# stepped-tone-generator.net
KiCad netlist of a schematic drawn in EAGLE
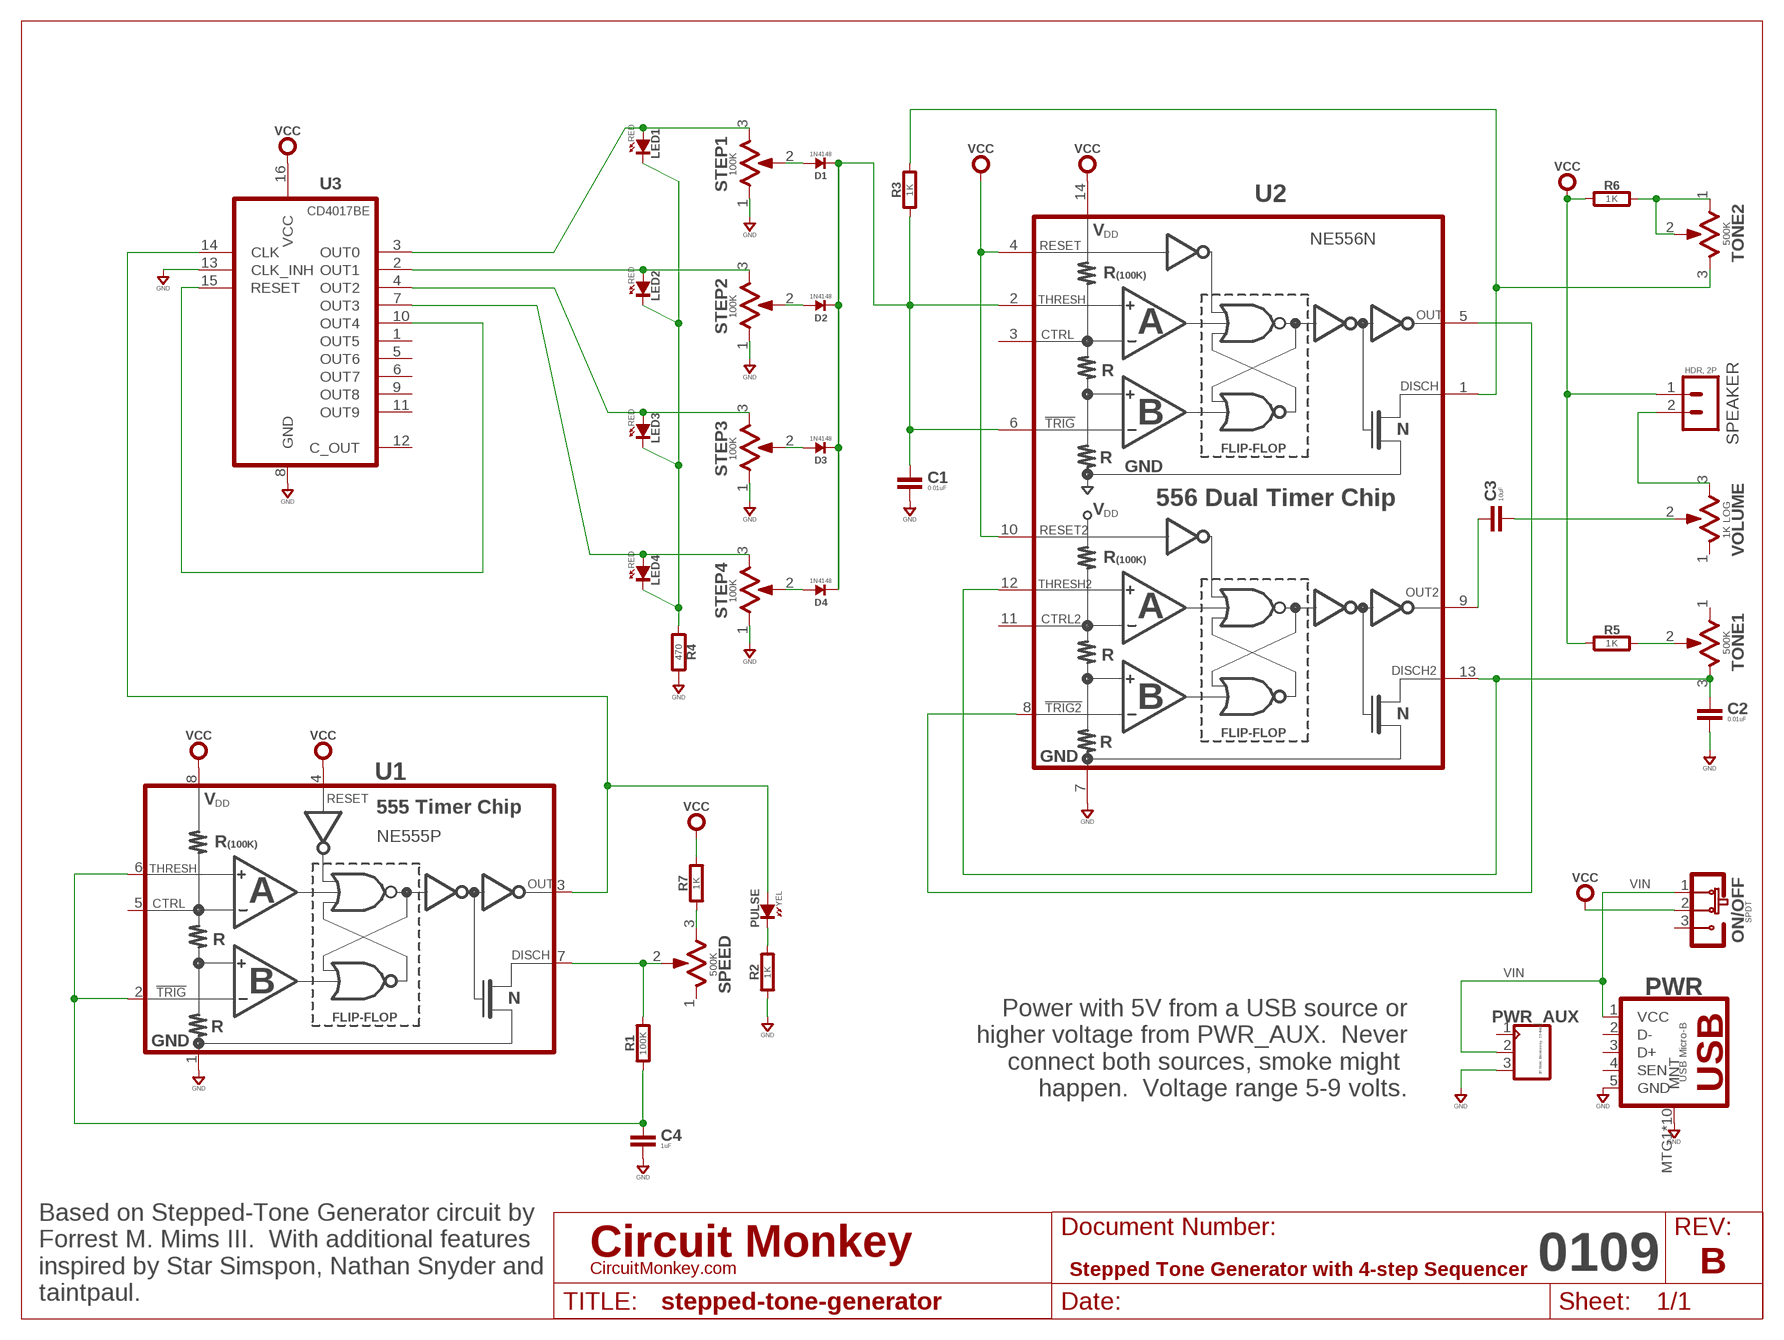
[diagram p0: schematic, sheet 1]

(export (version "E")
  (design (tool "Eeschema 10.0.6"))
  (components
    (comp (ref "C1")
      (value "0.01uF")
      (footprint "eagle-import:CAP_CER_THD_5MM")
      (fields (field (name "MFR") "Tayda") (field (name "MPN") "A-550"))
      (libsource (lib "eagle-import") (part "CAPACITORTHD_5MM"))
    )
    (comp (ref "C2")
      (value "0.01uF")
      (footprint "eagle-import:CAP_CER_THD_5MM")
      (fields (field (name "MFR") "Tayda") (field (name "MPN") "A-550"))
      (libsource (lib "eagle-import") (part "CAPACITORTHD_5MM"))
    )
    (comp (ref "C3")
      (value "10uF")
      (footprint "eagle-import:CAP_CER_THD_5MM")
      (fields (field (name "MFR") "Tayda") (field (name "MPN") "A-550"))
      (libsource (lib "eagle-import") (part "CAPACITORTHD_5MM"))
    )
    (comp (ref "C4")
      (value "1uF")
      (footprint "eagle-import:CAP_CER_THD_5MM")
      (fields (field (name "MFR") "Tayda") (field (name "MPN") "A-550"))
      (libsource (lib "eagle-import") (part "CAPACITORTHD_5MM"))
    )
    (comp (ref "D1")
      (value "1N4148")
      (footprint "eagle-import:DO-35(THD)")
      (fields (field (name "MFR") "Tayda") (field (name "MPN") "A-157"))
      (libsource (lib "eagle-import") (part "DIODE-1N4148-THD"))
    )
    (comp (ref "D2")
      (value "1N4148")
      (footprint "eagle-import:DO-35(THD)")
      (fields (field (name "MFR") "Tayda") (field (name "MPN") "A-157"))
      (libsource (lib "eagle-import") (part "DIODE-1N4148-THD"))
    )
    (comp (ref "D3")
      (value "1N4148")
      (footprint "eagle-import:DO-35(THD)")
      (fields (field (name "MFR") "Tayda") (field (name "MPN") "A-157"))
      (libsource (lib "eagle-import") (part "DIODE-1N4148-THD"))
    )
    (comp (ref "D4")
      (value "1N4148")
      (footprint "eagle-import:DO-35(THD)")
      (fields (field (name "MFR") "Tayda") (field (name "MPN") "A-157"))
      (libsource (lib "eagle-import") (part "DIODE-1N4148-THD"))
    )
    (comp (ref "LED1")
      (value "RED")
      (footprint "eagle-import:THD_3MM")
      (libsource (lib "eagle-import") (part "THD3MM"))
    )
    (comp (ref "LED2")
      (value "RED")
      (footprint "eagle-import:THD_3MM")
      (libsource (lib "eagle-import") (part "THD3MM"))
    )
    (comp (ref "LED3")
      (value "RED")
      (footprint "eagle-import:THD_3MM")
      (libsource (lib "eagle-import") (part "THD3MM"))
    )
    (comp (ref "LED4")
      (value "RED")
      (footprint "eagle-import:THD_3MM")
      (libsource (lib "eagle-import") (part "THD3MM"))
    )
    (comp (ref "ON/OFF")
      (value "SPDT")
      (footprint "eagle-import:MTS-102")
      (fields (field (name "MFR") "Tayda") (field (name "MPN") "A-4567"))
      (libsource (lib "eagle-import") (part "TOGGLEMTS-102"))
    )
    (comp (ref "PULSE")
      (value "YEL")
      (footprint "eagle-import:THD_3MM")
      (libsource (lib "eagle-import") (part "THD3MM"))
    )
    (comp (ref "PWR")
      (value "USB Micro-B")
      (footprint "eagle-import:JAE-DX4R005")
      (fields (field (name "MFR") "JAE") (field (name "MPN") "DX4R005JJ2R1800"))
      (libsource (lib "eagle-import") (part "USB-B-MICRO-SMTJAE-DX4R005"))
    )
    (comp (ref "PWR_AUX")
      (value "3P, Male, Breakaway, 2.54mm")
      (footprint "eagle-import:MA03X1-VT-THD")
      (libsource (lib "eagle-import") (part "CON_03X1-2.54MM-THD-VT"))
    )
    (comp (ref "R1")
      (value "100K")
      (footprint "eagle-import:R_THD_0.25W")
      (libsource (lib "eagle-import") (part "RESISTORTHD_0.25_WATT"))
    )
    (comp (ref "R2")
      (value "1K")
      (footprint "eagle-import:R_THD_0.25W")
      (libsource (lib "eagle-import") (part "RESISTORTHD_0.25_WATT"))
    )
    (comp (ref "R3")
      (value "1K")
      (footprint "eagle-import:R_THD_0.25W")
      (libsource (lib "eagle-import") (part "RESISTORTHD_0.25_WATT"))
    )
    (comp (ref "R4")
      (value "470")
      (footprint "eagle-import:R_THD_0.25W")
      (libsource (lib "eagle-import") (part "RESISTORTHD_0.25_WATT"))
    )
    (comp (ref "R5")
      (value "1K")
      (footprint "eagle-import:R_THD_0.25W")
      (libsource (lib "eagle-import") (part "RESISTORTHD_0.25_WATT"))
    )
    (comp (ref "R6")
      (value "1K")
      (footprint "eagle-import:R_THD_0.25W")
      (libsource (lib "eagle-import") (part "RESISTORTHD_0.25_WATT"))
    )
    (comp (ref "R7")
      (value "1K")
      (footprint "eagle-import:R_THD_0.25W")
      (libsource (lib "eagle-import") (part "RESISTORTHD_0.25_WATT"))
    )
    (comp (ref "SPEAKER")
      (value "HDR, 2P")
      (footprint "eagle-import:MA02-1-FAT")
      (libsource (lib "eagle-import") (part "MA02-1VT"))
    )
    (comp (ref "SPEED")
      (value "500K")
      (footprint "eagle-import:ALPS_RK09D113")
      (fields (field (name "MFR") "Alps") (field (name "MPN") "RK09D1130C1B"))
      (libsource (lib "eagle-import") (part "POTRK09?113"))
    )
    (comp (ref "STEP1")
      (value "100K")
      (footprint "eagle-import:ALPS_RK09D113")
      (fields (field (name "MFR") "Alps") (field (name "MPN") "RK09D1130C1B"))
      (libsource (lib "eagle-import") (part "POTRK09?113"))
    )
    (comp (ref "STEP2")
      (value "100K")
      (footprint "eagle-import:ALPS_RK09D113")
      (fields (field (name "MFR") "Alps") (field (name "MPN") "RK09D1130C1B"))
      (libsource (lib "eagle-import") (part "POTRK09?113"))
    )
    (comp (ref "STEP3")
      (value "100K")
      (footprint "eagle-import:ALPS_RK09D113")
      (fields (field (name "MFR") "Alps") (field (name "MPN") "RK09D1130C1B"))
      (libsource (lib "eagle-import") (part "POTRK09?113"))
    )
    (comp (ref "STEP4")
      (value "100K")
      (footprint "eagle-import:ALPS_RK09D113")
      (fields (field (name "MFR") "Alps") (field (name "MPN") "RK09D1130C1B"))
      (libsource (lib "eagle-import") (part "POTRK09?113"))
    )
    (comp (ref "TONE1")
      (value "500K")
      (footprint "eagle-import:ALPS_RK09D113")
      (fields (field (name "MFR") "Alps") (field (name "MPN") "RK09D1130C1B"))
      (libsource (lib "eagle-import") (part "POTRK09?113"))
    )
    (comp (ref "TONE2")
      (value "500K")
      (footprint "eagle-import:ALPS_RK09D113")
      (fields (field (name "MFR") "Alps") (field (name "MPN") "RK09D1130C1B"))
      (libsource (lib "eagle-import") (part "POTRK09?113"))
    )
    (comp (ref "U1")
      (value "NE555P")
      (footprint "eagle-import:DIP-08")
      (fields (field (name "MFR") "Tayda") (field (name "MPN") "A-249"))
      (libsource (lib "eagle-import") (part "555PDIP"))
    )
    (comp (ref "U2")
      (value "NE556N")
      (footprint "eagle-import:DIP-14")
      (fields (field (name "MFR") "Tayda") (field (name "MPN") "A-040") (field (name "SPICEPREFIX") "X"))
      (libsource (lib "eagle-import") (part "556PDIP"))
    )
    (comp (ref "U3")
      (value "CD4017BE")
      (footprint "eagle-import:DIP-16")
      (fields (field (name "MFR") "Tayda") (field (name "MPN") "A-020"))
      (libsource (lib "eagle-import") (part "CD4017PDIP"))
    )
    (comp (ref "VOLUME")
      (value "1K LOG")
      (footprint "eagle-import:ALPS_RK09D113")
      (fields (field (name "MFR") "Alps") (field (name "MPN") "RK09D1130C1B"))
      (libsource (lib "eagle-import") (part "POTRK09?113"))
    )
  )
  (nets
    (net (code "1") (name "/VIN") (class "Default")
      (node (ref "ON/OFF") (pin "1") (pinfunction "1_1") (pintype "bidirectional"))
      (node (ref "PWR") (pin "1") (pinfunction "VCC_1") (pintype "bidirectional"))
      (node (ref "PWR_AUX") (pin "2") (pinfunction "2_2") (pintype "passive"))
    )
    (net (code "2") (name "GND") (class "Default")
      (node (ref "C1") (pin "2") (pinfunction "2_2") (pintype "passive"))
      (node (ref "C2") (pin "2") (pinfunction "2_2") (pintype "passive"))
      (node (ref "C4") (pin "2") (pinfunction "2_2") (pintype "passive"))
      (node (ref "PWR") (pin "5") (pinfunction "GND_5") (pintype "bidirectional"))
      (node (ref "PWR") (pin "MTG1") (pinfunction "MNT_MTG1") (pintype "bidirectional"))
      (node (ref "PWR") (pin "MTG10") (pinfunction "MNT_MTG10") (pintype "bidirectional"))
      (node (ref "PWR") (pin "MTG2") (pinfunction "MNT_MTG2") (pintype "bidirectional"))
      (node (ref "PWR") (pin "MTG3") (pinfunction "MNT_MTG3") (pintype "bidirectional"))
      (node (ref "PWR") (pin "MTG4") (pinfunction "MNT_MTG4") (pintype "bidirectional"))
      (node (ref "PWR") (pin "MTG5") (pinfunction "MNT_MTG5") (pintype "bidirectional"))
      (node (ref "PWR") (pin "MTG6") (pinfunction "MNT_MTG6") (pintype "bidirectional"))
      (node (ref "PWR") (pin "MTG7") (pinfunction "MNT_MTG7") (pintype "bidirectional"))
      (node (ref "PWR") (pin "MTG8") (pinfunction "MNT_MTG8") (pintype "bidirectional"))
      (node (ref "PWR") (pin "MTG9") (pinfunction "MNT_MTG9") (pintype "bidirectional"))
      (node (ref "PWR_AUX") (pin "3") (pinfunction "3_3") (pintype "passive"))
      (node (ref "R2") (pin "1") (pinfunction "1_1") (pintype "passive"))
      (node (ref "R4") (pin "1") (pinfunction "1_1") (pintype "passive"))
      (node (ref "STEP1") (pin "1") (pinfunction "1_1") (pintype "passive"))
      (node (ref "STEP2") (pin "1") (pinfunction "1_1") (pintype "passive"))
      (node (ref "STEP3") (pin "1") (pinfunction "1_1") (pintype "passive"))
      (node (ref "STEP4") (pin "1") (pinfunction "1_1") (pintype "passive"))
      (node (ref "U1") (pin "1") (pinfunction "GND_1") (pintype "power_in"))
      (node (ref "U2") (pin "7") (pinfunction "GND_7") (pintype "power_in"))
      (node (ref "U3") (pin "13") (pinfunction "CLK_INH_13") (pintype "input"))
      (node (ref "U3") (pin "8") (pinfunction "GND_8") (pintype "power_in"))
    )
    (net (code "3") (name "Net-(C3-Pad2)") (class "Default")
      (node (ref "C3") (pin "2") (pinfunction "2_2") (pintype "passive"))
      (node (ref "VOLUME") (pin "2") (pinfunction "2_2") (pintype "passive"))
    )
    (net (code "4") (name "Net-(D1-PadA)") (class "Default")
      (node (ref "D1") (pin "A") (pinfunction "A_A") (pintype "passive"))
      (node (ref "STEP1") (pin "2") (pinfunction "2_2") (pintype "passive"))
    )
    (net (code "5") (name "Net-(D2-PadA)") (class "Default")
      (node (ref "D2") (pin "A") (pinfunction "A_A") (pintype "passive"))
      (node (ref "STEP2") (pin "2") (pinfunction "2_2") (pintype "passive"))
    )
    (net (code "6") (name "Net-(D3-PadA)") (class "Default")
      (node (ref "D3") (pin "A") (pinfunction "A_A") (pintype "passive"))
      (node (ref "STEP3") (pin "2") (pinfunction "2_2") (pintype "passive"))
    )
    (net (code "7") (name "Net-(D4-PadA)") (class "Default")
      (node (ref "D4") (pin "A") (pinfunction "A_A") (pintype "passive"))
      (node (ref "STEP4") (pin "2") (pinfunction "2_2") (pintype "passive"))
    )
    (net (code "8") (name "Net-(LED1-C)") (class "Default")
      (node (ref "LED1") (pin "K") (pinfunction "C_K") (pintype "passive"))
      (node (ref "LED2") (pin "K") (pinfunction "C_K") (pintype "passive"))
      (node (ref "LED3") (pin "K") (pinfunction "C_K") (pintype "passive"))
      (node (ref "LED4") (pin "K") (pinfunction "C_K") (pintype "passive"))
      (node (ref "R4") (pin "2") (pinfunction "2_2") (pintype "passive"))
    )
    (net (code "9") (name "Net-(PULSE-C)") (class "Default")
      (node (ref "PULSE") (pin "K") (pinfunction "C_K") (pintype "passive"))
      (node (ref "R2") (pin "2") (pinfunction "2_2") (pintype "passive"))
    )
    (net (code "10") (name "Net-(R5-Pad2)") (class "Default")
      (node (ref "R5") (pin "2") (pinfunction "2_2") (pintype "passive"))
      (node (ref "TONE1") (pin "2") (pinfunction "2_2") (pintype "passive"))
    )
    (net (code "11") (name "Net-(R6-Pad2)") (class "Default")
      (node (ref "R6") (pin "2") (pinfunction "2_2") (pintype "passive"))
      (node (ref "TONE2") (pin "1") (pinfunction "1_1") (pintype "passive"))
      (node (ref "TONE2") (pin "2") (pinfunction "2_2") (pintype "passive"))
    )
    (net (code "12") (name "Net-(R7-Pad1)") (class "Default")
      (node (ref "R7") (pin "1") (pinfunction "1_1") (pintype "passive"))
      (node (ref "SPEED") (pin "3") (pinfunction "3_3") (pintype "passive"))
    )
    (net (code "13") (name "Net-(SPEAKER-Pad2)") (class "Default")
      (node (ref "SPEAKER") (pin "2") (pinfunction "2_2") (pintype "passive"))
      (node (ref "VOLUME") (pin "3") (pinfunction "3_3") (pintype "passive"))
    )
    (net (code "14") (name "Net-(U1-DISCHARGE)") (class "Default")
      (node (ref "R1") (pin "2") (pinfunction "2_2") (pintype "passive"))
      (node (ref "SPEED") (pin "2") (pinfunction "2_2") (pintype "passive"))
      (node (ref "U1") (pin "7") (pinfunction "DISCHARGE_7") (pintype "output"))
    )
    (net (code "15") (name "Net-(U1-OUTPUT)") (class "Default")
      (node (ref "PULSE") (pin "A") (pinfunction "A_A") (pintype "passive"))
      (node (ref "U1") (pin "3") (pinfunction "OUTPUT_3") (pintype "output"))
      (node (ref "U3") (pin "14") (pinfunction "CLK_14") (pintype "input"))
    )
    (net (code "16") (name "Net-(U1-THRESHOLD)") (class "Default")
      (node (ref "C4") (pin "1") (pinfunction "1_1") (pintype "passive"))
      (node (ref "R1") (pin "1") (pinfunction "1_1") (pintype "passive"))
      (node (ref "U1") (pin "2") (pinfunction "TRIGGER#_2") (pintype "input"))
      (node (ref "U1") (pin "6") (pinfunction "THRESHOLD_6") (pintype "input"))
    )
    (net (code "17") (name "Net-(U2-DISCHARGE)") (class "Default")
      (node (ref "R3") (pin "2") (pinfunction "2_2") (pintype "passive"))
      (node (ref "TONE2") (pin "3") (pinfunction "3_3") (pintype "passive"))
      (node (ref "U2") (pin "1") (pinfunction "DISCHARGE_1") (pintype "output"))
    )
    (net (code "18") (name "Net-(U2-DISCHARGE2)") (class "Default")
      (node (ref "C2") (pin "1") (pinfunction "1_1") (pintype "passive"))
      (node (ref "TONE1") (pin "3") (pinfunction "3_3") (pintype "passive"))
      (node (ref "U2") (pin "12") (pinfunction "THRESHOLD2_12") (pintype "input"))
      (node (ref "U2") (pin "13") (pinfunction "DISCHARGE2_13") (pintype "output"))
    )
    (net (code "19") (name "Net-(U2-OUTPUT)") (class "Default")
      (node (ref "U2") (pin "5") (pinfunction "OUTPUT_5") (pintype "output"))
      (node (ref "U2") (pin "8") (pinfunction "TRIGGER2#_8") (pintype "input"))
    )
    (net (code "20") (name "Net-(U2-OUTPUT2)") (class "Default")
      (node (ref "C3") (pin "1") (pinfunction "1_1") (pintype "passive"))
      (node (ref "U2") (pin "9") (pinfunction "OUTPUT2_9") (pintype "output"))
    )
    (net (code "21") (name "Net-(U2-THRESHOLD)") (class "Default")
      (node (ref "C1") (pin "1") (pinfunction "1_1") (pintype "passive"))
      (node (ref "D1") (pin "K") (pinfunction "K_K") (pintype "passive"))
      (node (ref "D2") (pin "K") (pinfunction "K_K") (pintype "passive"))
      (node (ref "D3") (pin "K") (pinfunction "K_K") (pintype "passive"))
      (node (ref "D4") (pin "K") (pinfunction "K_K") (pintype "passive"))
      (node (ref "R3") (pin "1") (pinfunction "1_1") (pintype "passive"))
      (node (ref "U2") (pin "2") (pinfunction "THRESHOLD_2") (pintype "input"))
      (node (ref "U2") (pin "6") (pinfunction "TRIGGER#_6") (pintype "input"))
    )
    (net (code "22") (name "Net-(U3-OUT0)") (class "Default")
      (node (ref "LED1") (pin "A") (pinfunction "A_A") (pintype "passive"))
      (node (ref "STEP1") (pin "3") (pinfunction "3_3") (pintype "passive"))
      (node (ref "U3") (pin "3") (pinfunction "OUT0_3") (pintype "output"))
    )
    (net (code "23") (name "Net-(U3-OUT1)") (class "Default")
      (node (ref "LED2") (pin "A") (pinfunction "A_A") (pintype "passive"))
      (node (ref "STEP2") (pin "3") (pinfunction "3_3") (pintype "passive"))
      (node (ref "U3") (pin "2") (pinfunction "OUT1_2") (pintype "output"))
    )
    (net (code "24") (name "Net-(U3-OUT2)") (class "Default")
      (node (ref "LED3") (pin "A") (pinfunction "A_A") (pintype "passive"))
      (node (ref "STEP3") (pin "3") (pinfunction "3_3") (pintype "passive"))
      (node (ref "U3") (pin "4") (pinfunction "OUT2_4") (pintype "output"))
    )
    (net (code "25") (name "Net-(U3-OUT3)") (class "Default")
      (node (ref "LED4") (pin "A") (pinfunction "A_A") (pintype "passive"))
      (node (ref "STEP4") (pin "3") (pinfunction "3_3") (pintype "passive"))
      (node (ref "U3") (pin "7") (pinfunction "OUT3_7") (pintype "output"))
    )
    (net (code "26") (name "Net-(U3-OUT4)") (class "Default")
      (node (ref "U3") (pin "10") (pinfunction "OUT4_10") (pintype "output"))
      (node (ref "U3") (pin "15") (pinfunction "RESET_15") (pintype "input"))
    )
    (net (code "27") (name "VCC") (class "Default")
      (node (ref "ON/OFF") (pin "2") (pinfunction "2_2") (pintype "bidirectional"))
      (node (ref "R5") (pin "1") (pinfunction "1_1") (pintype "passive"))
      (node (ref "R6") (pin "1") (pinfunction "1_1") (pintype "passive"))
      (node (ref "R7") (pin "2") (pinfunction "2_2") (pintype "passive"))
      (node (ref "SPEAKER") (pin "1") (pinfunction "1_1") (pintype "passive"))
      (node (ref "U1") (pin "4") (pinfunction "RESET#_4") (pintype "bidirectional"))
      (node (ref "U1") (pin "8") (pinfunction "VDD_8") (pintype "power_in"))
      (node (ref "U2") (pin "10") (pinfunction "RESET2_10") (pintype "bidirectional"))
      (node (ref "U2") (pin "14") (pinfunction "VDD_14") (pintype "power_in"))
      (node (ref "U2") (pin "4") (pinfunction "RESET#_4") (pintype "bidirectional"))
      (node (ref "U3") (pin "16") (pinfunction "VCC_16") (pintype "power_in"))
    )
    (net (code "28") (name "unconnected-(ON/OFF-Pad3)") (class "Default")
      (node (ref "ON/OFF") (pin "3") (pinfunction "3_3") (pintype "bidirectional"))
    )
    (net (code "29") (name "unconnected-(PWR-D+-Pad3)") (class "Default")
      (node (ref "PWR") (pin "3") (pinfunction "D+_3") (pintype "bidirectional"))
    )
    (net (code "30") (name "unconnected-(PWR-D--Pad2)") (class "Default")
      (node (ref "PWR") (pin "2") (pinfunction "D-_2") (pintype "bidirectional"))
    )
    (net (code "31") (name "unconnected-(PWR-SEN-Pad4)") (class "Default")
      (node (ref "PWR") (pin "4") (pinfunction "SEN_4") (pintype "bidirectional"))
    )
    (net (code "32") (name "unconnected-(PWR_AUX-Pad1)") (class "Default")
      (node (ref "PWR_AUX") (pin "1") (pinfunction "1_1") (pintype "passive"))
    )
    (net (code "33") (name "unconnected-(SPEED-Pad1)") (class "Default")
      (node (ref "SPEED") (pin "1") (pinfunction "1_1") (pintype "passive"))
    )
    (net (code "34") (name "unconnected-(TONE1-Pad1)") (class "Default")
      (node (ref "TONE1") (pin "1") (pinfunction "1_1") (pintype "passive"))
    )
    (net (code "35") (name "unconnected-(U1-CONTROL-Pad5)") (class "Default")
      (node (ref "U1") (pin "5") (pinfunction "CONTROL_5") (pintype "input"))
    )
    (net (code "36") (name "unconnected-(U2-CONTROL-Pad3)") (class "Default")
      (node (ref "U2") (pin "3") (pinfunction "CONTROL_3") (pintype "input"))
    )
    (net (code "37") (name "unconnected-(U2-CONTROL2#-Pad11)") (class "Default")
      (node (ref "U2") (pin "11") (pinfunction "CONTROL2#_11") (pintype "input"))
    )
    (net (code "38") (name "unconnected-(U3-C_OUT-Pad12)") (class "Default")
      (node (ref "U3") (pin "12") (pinfunction "C_OUT_12") (pintype "output"))
    )
    (net (code "39") (name "unconnected-(U3-OUT5-Pad1)") (class "Default")
      (node (ref "U3") (pin "1") (pinfunction "OUT5_1") (pintype "output"))
    )
    (net (code "40") (name "unconnected-(U3-OUT6-Pad5)") (class "Default")
      (node (ref "U3") (pin "5") (pinfunction "OUT6_5") (pintype "output"))
    )
    (net (code "41") (name "unconnected-(U3-OUT7-Pad6)") (class "Default")
      (node (ref "U3") (pin "6") (pinfunction "OUT7_6") (pintype "output"))
    )
    (net (code "42") (name "unconnected-(U3-OUT8-Pad9)") (class "Default")
      (node (ref "U3") (pin "9") (pinfunction "OUT8_9") (pintype "output"))
    )
    (net (code "43") (name "unconnected-(U3-OUT9-Pad11)") (class "Default")
      (node (ref "U3") (pin "11") (pinfunction "OUT9_11") (pintype "output"))
    )
    (net (code "44") (name "unconnected-(VOLUME-Pad1)") (class "Default")
      (node (ref "VOLUME") (pin "1") (pinfunction "1_1") (pintype "passive"))
    )
  )
)
